# LED_BOARD.net
KiCad netlist of a schematic drawn in EAGLE
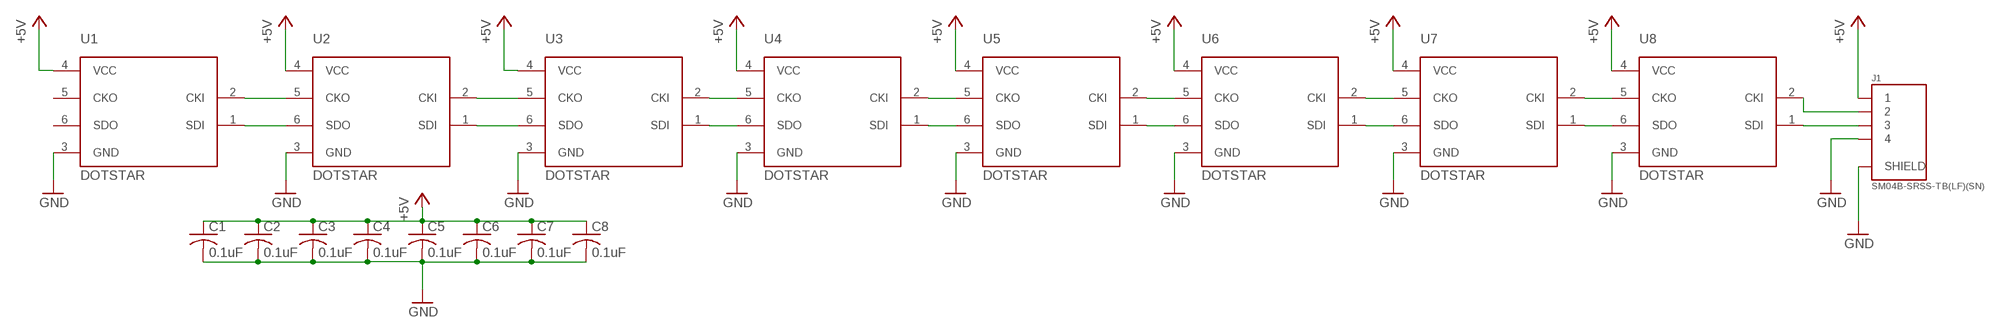
[diagram p0: schematic, sheet 1]

(export (version "E")
  (design (tool "Eeschema 10.0.6"))
  (components
    (comp (ref "C1")
      (value "0.1uF")
      (footprint "eagle-import:C0603")
      (libsource (lib "eagle-import") (part "C-USC0603"))
    )
    (comp (ref "C2")
      (value "0.1uF")
      (footprint "eagle-import:C0603")
      (libsource (lib "eagle-import") (part "C-USC0603"))
    )
    (comp (ref "C3")
      (value "0.1uF")
      (footprint "eagle-import:C0603")
      (libsource (lib "eagle-import") (part "C-USC0603"))
    )
    (comp (ref "C4")
      (value "0.1uF")
      (footprint "eagle-import:C0603")
      (libsource (lib "eagle-import") (part "C-USC0603"))
    )
    (comp (ref "C5")
      (value "0.1uF")
      (footprint "eagle-import:C0603")
      (libsource (lib "eagle-import") (part "C-USC0603"))
    )
    (comp (ref "C6")
      (value "0.1uF")
      (footprint "eagle-import:C0603")
      (libsource (lib "eagle-import") (part "C-USC0603"))
    )
    (comp (ref "C7")
      (value "0.1uF")
      (footprint "eagle-import:C0603")
      (libsource (lib "eagle-import") (part "C-USC0603"))
    )
    (comp (ref "C8")
      (value "0.1uF")
      (footprint "eagle-import:C0603")
      (libsource (lib "eagle-import") (part "C-USC0603"))
    )
    (comp (ref "J1")
      (value "SM04B-SRSS-TB(LF)(SN)")
      (footprint "eagle-import:SM04B-SRSS-TB(LF)(SN)")
      (libsource (lib "eagle-import") (part "SM04B-SRSS-TB(LF)(SN)"))
    )
    (comp (ref "U1")
      (value "DOTSTAR")
      (footprint "eagle-import:RGBLED5050")
      (libsource (lib "eagle-import") (part "DOTSTAR"))
    )
    (comp (ref "U2")
      (value "DOTSTAR")
      (footprint "eagle-import:RGBLED5050")
      (libsource (lib "eagle-import") (part "DOTSTAR"))
    )
    (comp (ref "U3")
      (value "DOTSTAR")
      (footprint "eagle-import:RGBLED5050")
      (libsource (lib "eagle-import") (part "DOTSTAR"))
    )
    (comp (ref "U4")
      (value "DOTSTAR")
      (footprint "eagle-import:RGBLED5050")
      (libsource (lib "eagle-import") (part "DOTSTAR"))
    )
    (comp (ref "U5")
      (value "DOTSTAR")
      (footprint "eagle-import:RGBLED5050")
      (libsource (lib "eagle-import") (part "DOTSTAR"))
    )
    (comp (ref "U6")
      (value "DOTSTAR")
      (footprint "eagle-import:RGBLED5050")
      (libsource (lib "eagle-import") (part "DOTSTAR"))
    )
    (comp (ref "U7")
      (value "DOTSTAR")
      (footprint "eagle-import:RGBLED5050")
      (libsource (lib "eagle-import") (part "DOTSTAR"))
    )
    (comp (ref "U8")
      (value "DOTSTAR")
      (footprint "eagle-import:RGBLED5050")
      (libsource (lib "eagle-import") (part "DOTSTAR"))
    )
  )
  (nets
    (net (code "1") (name "+5V") (class "Default")
      (node (ref "C1") (pin "1") (pinfunction "1_1") (pintype "passive"))
      (node (ref "C2") (pin "1") (pinfunction "1_1") (pintype "passive"))
      (node (ref "C3") (pin "1") (pinfunction "1_1") (pintype "passive"))
      (node (ref "C4") (pin "1") (pinfunction "1_1") (pintype "passive"))
      (node (ref "C5") (pin "1") (pinfunction "1_1") (pintype "passive"))
      (node (ref "C6") (pin "1") (pinfunction "1_1") (pintype "passive"))
      (node (ref "C7") (pin "1") (pinfunction "1_1") (pintype "passive"))
      (node (ref "C8") (pin "1") (pinfunction "1_1") (pintype "passive"))
      (node (ref "J1") (pin "1") (pinfunction "1_1") (pintype "passive"))
      (node (ref "U1") (pin "4") (pinfunction "VCC_4") (pintype "bidirectional"))
      (node (ref "U2") (pin "4") (pinfunction "VCC_4") (pintype "bidirectional"))
      (node (ref "U3") (pin "4") (pinfunction "VCC_4") (pintype "bidirectional"))
      (node (ref "U4") (pin "4") (pinfunction "VCC_4") (pintype "bidirectional"))
      (node (ref "U5") (pin "4") (pinfunction "VCC_4") (pintype "bidirectional"))
      (node (ref "U6") (pin "4") (pinfunction "VCC_4") (pintype "bidirectional"))
      (node (ref "U7") (pin "4") (pinfunction "VCC_4") (pintype "bidirectional"))
      (node (ref "U8") (pin "4") (pinfunction "VCC_4") (pintype "bidirectional"))
    )
    (net (code "2") (name "GND") (class "Default")
      (node (ref "C1") (pin "2") (pinfunction "2_2") (pintype "passive"))
      (node (ref "C2") (pin "2") (pinfunction "2_2") (pintype "passive"))
      (node (ref "C3") (pin "2") (pinfunction "2_2") (pintype "passive"))
      (node (ref "C4") (pin "2") (pinfunction "2_2") (pintype "passive"))
      (node (ref "C5") (pin "2") (pinfunction "2_2") (pintype "passive"))
      (node (ref "C6") (pin "2") (pinfunction "2_2") (pintype "passive"))
      (node (ref "C7") (pin "2") (pinfunction "2_2") (pintype "passive"))
      (node (ref "C8") (pin "2") (pinfunction "2_2") (pintype "passive"))
      (node (ref "J1") (pin "4") (pinfunction "4_4") (pintype "passive"))
      (node (ref "J1") (pin "S1") (pinfunction "SHIELD_S1") (pintype "passive"))
      (node (ref "J1") (pin "S2") (pinfunction "SHIELD_S2") (pintype "passive"))
      (node (ref "U1") (pin "3") (pinfunction "GND_3") (pintype "bidirectional"))
      (node (ref "U2") (pin "3") (pinfunction "GND_3") (pintype "bidirectional"))
      (node (ref "U3") (pin "3") (pinfunction "GND_3") (pintype "bidirectional"))
      (node (ref "U4") (pin "3") (pinfunction "GND_3") (pintype "bidirectional"))
      (node (ref "U5") (pin "3") (pinfunction "GND_3") (pintype "bidirectional"))
      (node (ref "U6") (pin "3") (pinfunction "GND_3") (pintype "bidirectional"))
      (node (ref "U7") (pin "3") (pinfunction "GND_3") (pintype "bidirectional"))
      (node (ref "U8") (pin "3") (pinfunction "GND_3") (pintype "bidirectional"))
    )
    (net (code "3") (name "Net-(U1-CKI)") (class "Default")
      (node (ref "U1") (pin "2") (pinfunction "CKI_2") (pintype "bidirectional"))
      (node (ref "U2") (pin "5") (pinfunction "CKO_5") (pintype "bidirectional"))
    )
    (net (code "4") (name "Net-(U1-SDI)") (class "Default")
      (node (ref "U1") (pin "1") (pinfunction "SDI_1") (pintype "bidirectional"))
      (node (ref "U2") (pin "6") (pinfunction "SDO_6") (pintype "bidirectional"))
    )
    (net (code "5") (name "Net-(U2-CKI)") (class "Default")
      (node (ref "U2") (pin "2") (pinfunction "CKI_2") (pintype "bidirectional"))
      (node (ref "U3") (pin "5") (pinfunction "CKO_5") (pintype "bidirectional"))
    )
    (net (code "6") (name "Net-(U2-SDI)") (class "Default")
      (node (ref "U2") (pin "1") (pinfunction "SDI_1") (pintype "bidirectional"))
      (node (ref "U3") (pin "6") (pinfunction "SDO_6") (pintype "bidirectional"))
    )
    (net (code "7") (name "Net-(U3-CKI)") (class "Default")
      (node (ref "U3") (pin "2") (pinfunction "CKI_2") (pintype "bidirectional"))
      (node (ref "U4") (pin "5") (pinfunction "CKO_5") (pintype "bidirectional"))
    )
    (net (code "8") (name "Net-(U3-SDI)") (class "Default")
      (node (ref "U3") (pin "1") (pinfunction "SDI_1") (pintype "bidirectional"))
      (node (ref "U4") (pin "6") (pinfunction "SDO_6") (pintype "bidirectional"))
    )
    (net (code "9") (name "Net-(U4-CKI)") (class "Default")
      (node (ref "U4") (pin "2") (pinfunction "CKI_2") (pintype "bidirectional"))
      (node (ref "U5") (pin "5") (pinfunction "CKO_5") (pintype "bidirectional"))
    )
    (net (code "10") (name "Net-(U4-SDI)") (class "Default")
      (node (ref "U4") (pin "1") (pinfunction "SDI_1") (pintype "bidirectional"))
      (node (ref "U5") (pin "6") (pinfunction "SDO_6") (pintype "bidirectional"))
    )
    (net (code "11") (name "Net-(U5-CKI)") (class "Default")
      (node (ref "U5") (pin "2") (pinfunction "CKI_2") (pintype "bidirectional"))
      (node (ref "U6") (pin "5") (pinfunction "CKO_5") (pintype "bidirectional"))
    )
    (net (code "12") (name "Net-(U5-SDI)") (class "Default")
      (node (ref "U5") (pin "1") (pinfunction "SDI_1") (pintype "bidirectional"))
      (node (ref "U6") (pin "6") (pinfunction "SDO_6") (pintype "bidirectional"))
    )
    (net (code "13") (name "Net-(U6-CKI)") (class "Default")
      (node (ref "U6") (pin "2") (pinfunction "CKI_2") (pintype "bidirectional"))
      (node (ref "U7") (pin "5") (pinfunction "CKO_5") (pintype "bidirectional"))
    )
    (net (code "14") (name "Net-(U6-SDI)") (class "Default")
      (node (ref "U6") (pin "1") (pinfunction "SDI_1") (pintype "bidirectional"))
      (node (ref "U7") (pin "6") (pinfunction "SDO_6") (pintype "bidirectional"))
    )
    (net (code "15") (name "Net-(U7-CKI)") (class "Default")
      (node (ref "U7") (pin "2") (pinfunction "CKI_2") (pintype "bidirectional"))
      (node (ref "U8") (pin "5") (pinfunction "CKO_5") (pintype "bidirectional"))
    )
    (net (code "16") (name "Net-(U7-SDI)") (class "Default")
      (node (ref "U7") (pin "1") (pinfunction "SDI_1") (pintype "bidirectional"))
      (node (ref "U8") (pin "6") (pinfunction "SDO_6") (pintype "bidirectional"))
    )
    (net (code "17") (name "Net-(U8-CKI)") (class "Default")
      (node (ref "J1") (pin "2") (pinfunction "2_2") (pintype "passive"))
      (node (ref "U8") (pin "2") (pinfunction "CKI_2") (pintype "bidirectional"))
    )
    (net (code "18") (name "Net-(U8-SDI)") (class "Default")
      (node (ref "J1") (pin "3") (pinfunction "3_3") (pintype "passive"))
      (node (ref "U8") (pin "1") (pinfunction "SDI_1") (pintype "bidirectional"))
    )
    (net (code "19") (name "unconnected-(U1-CKO-Pad5)") (class "Default")
      (node (ref "U1") (pin "5") (pinfunction "CKO_5") (pintype "bidirectional"))
    )
    (net (code "20") (name "unconnected-(U1-SDO-Pad6)") (class "Default")
      (node (ref "U1") (pin "6") (pinfunction "SDO_6") (pintype "bidirectional"))
    )
  )
)
